# buzzer_breakout.net
KiCad netlist of a schematic drawn in EAGLE
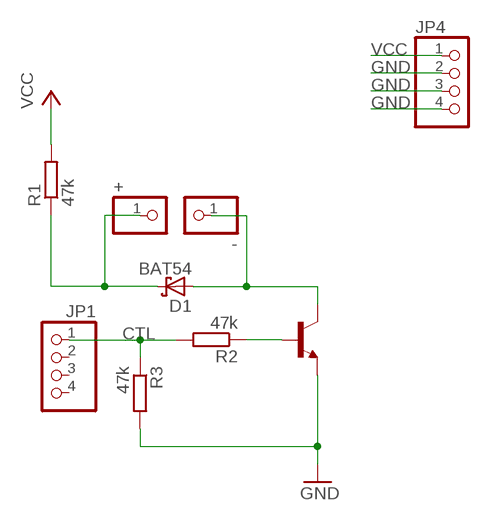
[diagram p0: schematic, sheet 1]

(export (version "E")
  (design (tool "Eeschema 10.0.6"))
  (components
    (comp (ref "+")
      (value "PINHD-1X1")
      (footprint "eagle-import:1X01")
      (libsource (lib "eagle-import") (part "PINHD-1X1"))
    )
    (comp (ref "-")
      (value "PINHD-1X1")
      (footprint "eagle-import:1X01")
      (libsource (lib "eagle-import") (part "PINHD-1X1"))
    )
    (comp (ref "D1")
      (value "BAT54")
      (footprint "eagle-import:SOT23")
      (libsource (lib "eagle-import") (part "BAT54"))
    )
    (comp (ref "JP1")
      (value "PINHD-1X4")
      (footprint "eagle-import:1X04")
      (libsource (lib "eagle-import") (part "PINHD-1X4"))
    )
    (comp (ref "JP4")
      (value "PINHD-1X4")
      (footprint "eagle-import:1X04")
      (libsource (lib "eagle-import") (part "PINHD-1X4"))
    )
    (comp (ref "R1")
      (value "47k")
      (footprint "eagle-import:R0805")
      (libsource (lib "eagle-import") (part "R-EU_R0805"))
    )
    (comp (ref "R2")
      (value "47k")
      (footprint "eagle-import:R0805")
      (libsource (lib "eagle-import") (part "R-EU_R0805"))
    )
    (comp (ref "R3")
      (value "47k")
      (footprint "eagle-import:R0805")
      (libsource (lib "eagle-import") (part "R-EU_R0805"))
    )
    (comp (ref "T1")
      (value "BC817-16-NPN-SOT23-BEC")
      (footprint "eagle-import:SOT23-BEC")
      (libsource (lib "eagle-import") (part "-NPN-SOT23-BECBC817-16"))
    )
  )
  (nets
    (net (code "1") (name "/CTL") (class "Default")
      (node (ref "JP1") (pin "1") (pinfunction "1_1") (pintype "passive"))
      (node (ref "R2") (pin "2") (pinfunction "2_2") (pintype "passive"))
      (node (ref "R3") (pin "1") (pinfunction "1_1") (pintype "passive"))
    )
    (net (code "2") (name "GND") (class "Default")
      (node (ref "JP4") (pin "2") (pinfunction "2_2") (pintype "passive"))
      (node (ref "JP4") (pin "3") (pinfunction "3_3") (pintype "passive"))
      (node (ref "JP4") (pin "4") (pinfunction "4_4") (pintype "passive"))
      (node (ref "R3") (pin "2") (pinfunction "2_2") (pintype "passive"))
      (node (ref "T1") (pin "E") (pinfunction "E_E") (pintype "passive"))
    )
    (net (code "3") (name "Net-(D1-A)") (class "Default")
      (node (ref "-") (pin "1") (pinfunction "1_1") (pintype "passive"))
      (node (ref "D1") (pin "1") (pinfunction "A_1") (pintype "passive"))
      (node (ref "T1") (pin "C") (pinfunction "C_C") (pintype "passive"))
    )
    (net (code "4") (name "Net-(D1-C)") (class "Default")
      (node (ref "+") (pin "1") (pinfunction "1_1") (pintype "passive"))
      (node (ref "D1") (pin "3") (pinfunction "C_3") (pintype "passive"))
      (node (ref "R1") (pin "1") (pinfunction "1_1") (pintype "passive"))
    )
    (net (code "5") (name "Net-(R2-Pad1)") (class "Default")
      (node (ref "R2") (pin "1") (pinfunction "1_1") (pintype "passive"))
      (node (ref "T1") (pin "B") (pinfunction "B_B") (pintype "passive"))
    )
    (net (code "6") (name "VCC") (class "Default")
      (node (ref "JP4") (pin "1") (pinfunction "1_1") (pintype "passive"))
      (node (ref "R1") (pin "2") (pinfunction "2_2") (pintype "passive"))
    )
    (net (code "7") (name "unconnected-(JP1-Pad2)") (class "Default")
      (node (ref "JP1") (pin "2") (pinfunction "2_2") (pintype "passive"))
    )
    (net (code "8") (name "unconnected-(JP1-Pad3)") (class "Default")
      (node (ref "JP1") (pin "3") (pinfunction "3_3") (pintype "passive"))
    )
    (net (code "9") (name "unconnected-(JP1-Pad4)") (class "Default")
      (node (ref "JP1") (pin "4") (pinfunction "4_4") (pintype "passive"))
    )
  )
)
